# tinyTHP.net
KiCad netlist of a schematic drawn in EAGLE
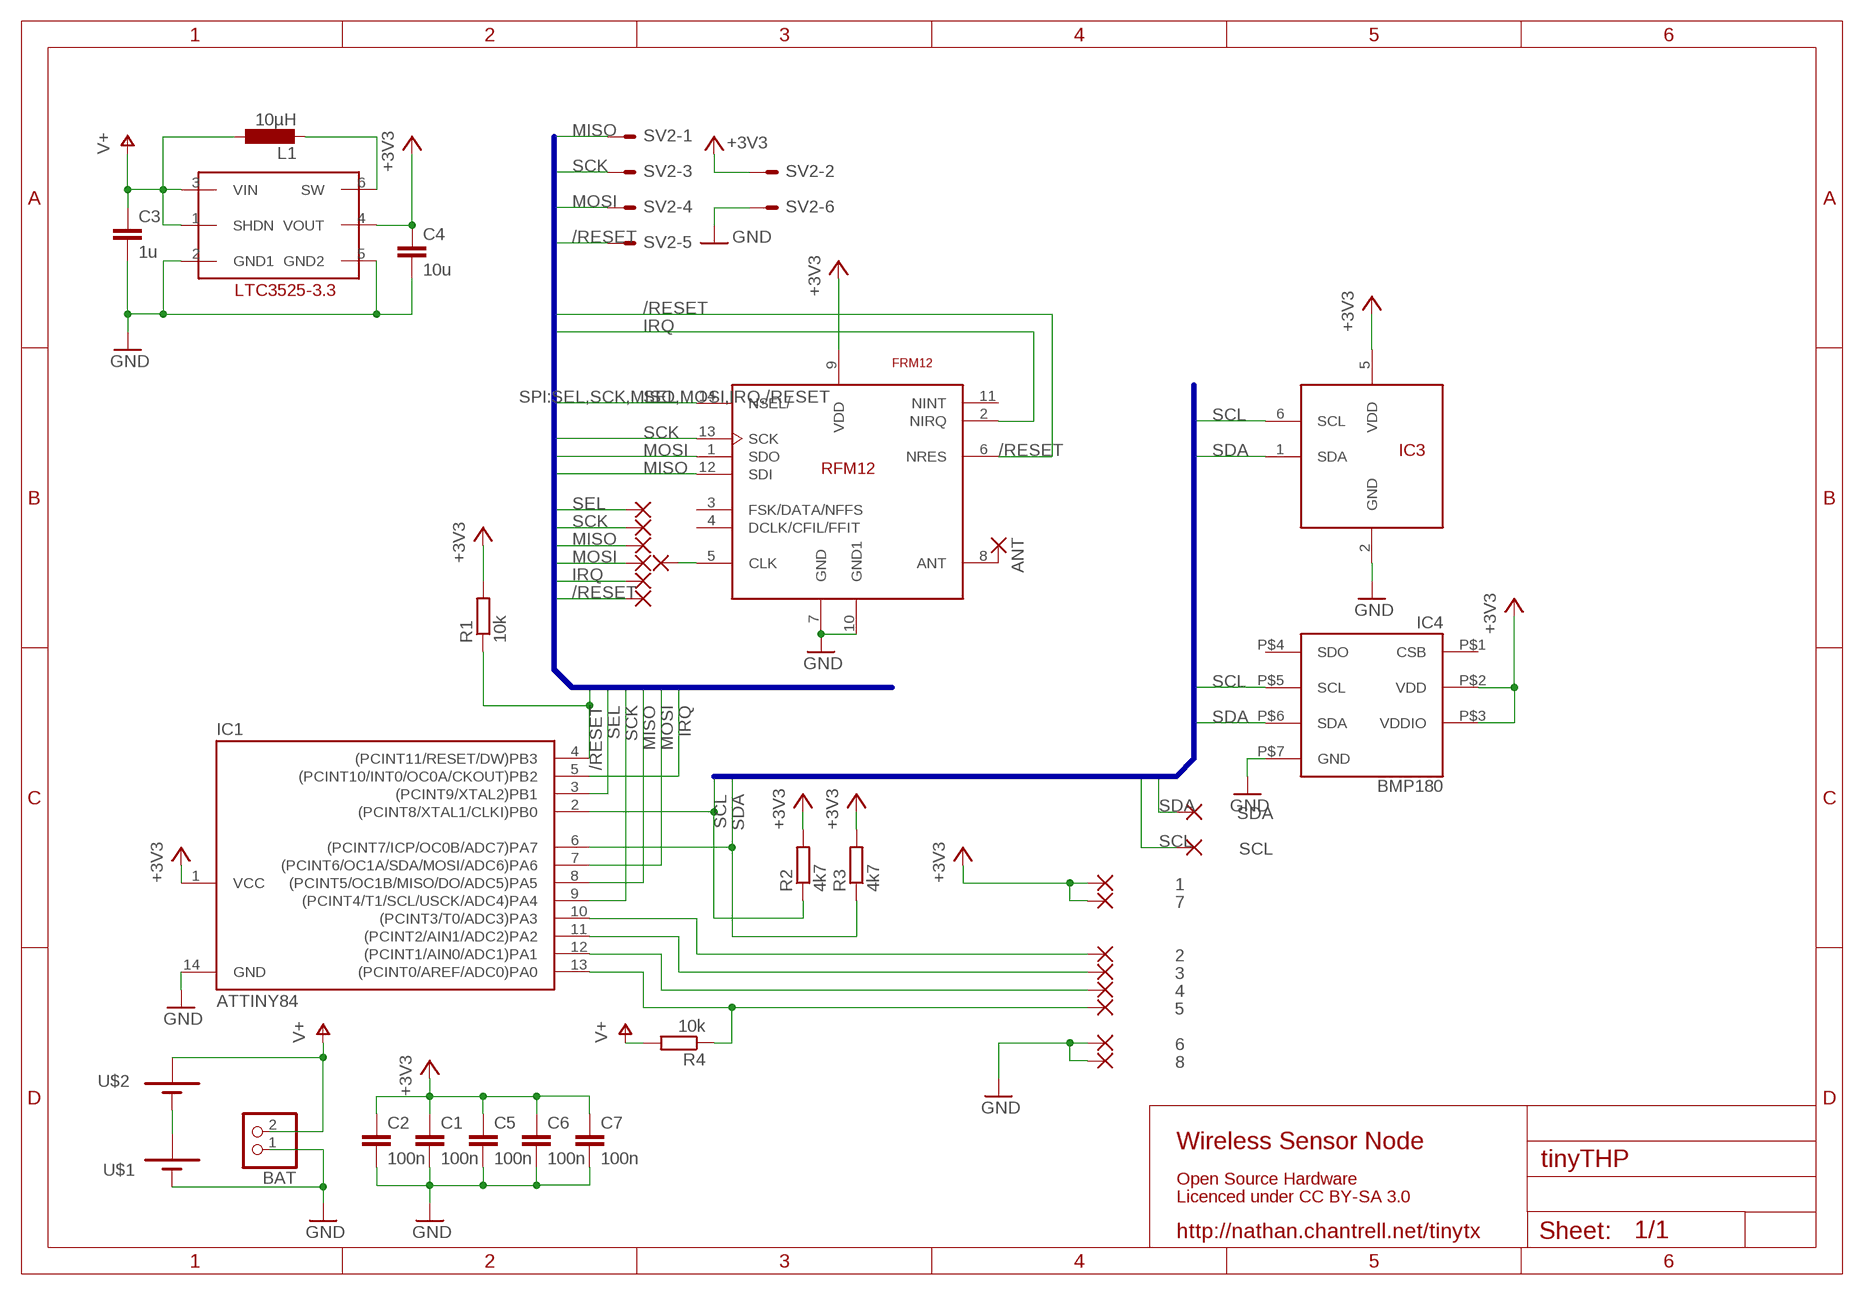
[diagram p0: schematic, sheet 1]

(export (version "E")
  (design (tool "Eeschema 10.0.6"))
  (components
    (comp (ref "/IRQ")
      (value "1,6/0,9")
      (footprint "eagle-import:1,6_0,9")
      (libsource (lib "eagle-import") (part "1,6/0,9"))
    )
    (comp (ref "/RESET")
      (value "1,6/0,9")
      (footprint "eagle-import:1,6_0,9")
      (libsource (lib "eagle-import") (part "1,6/0,9"))
    )
    (comp (ref "1")
      (value "1,6/0,9")
      (footprint "eagle-import:1,6_0,9")
      (libsource (lib "eagle-import") (part "1,6/0,9"))
    )
    (comp (ref "2")
      (value "1,6/0,9")
      (footprint "eagle-import:1,6_0,9")
      (libsource (lib "eagle-import") (part "1,6/0,9"))
    )
    (comp (ref "3")
      (value "1,6/0,9")
      (footprint "eagle-import:1,6_0,9")
      (libsource (lib "eagle-import") (part "1,6/0,9"))
    )
    (comp (ref "4")
      (value "1,6/0,9")
      (footprint "eagle-import:1,6_0,9")
      (libsource (lib "eagle-import") (part "1,6/0,9"))
    )
    (comp (ref "5")
      (value "1,6/0,9")
      (footprint "eagle-import:1,6_0,9")
      (libsource (lib "eagle-import") (part "1,6/0,9"))
    )
    (comp (ref "6")
      (value "1,6/0,9")
      (footprint "eagle-import:1,6_0,9")
      (libsource (lib "eagle-import") (part "1,6/0,9"))
    )
    (comp (ref "7")
      (value "1,6/0,9")
      (footprint "eagle-import:1,6_0,9")
      (libsource (lib "eagle-import") (part "1,6/0,9"))
    )
    (comp (ref "8")
      (value "1,6/0,9")
      (footprint "eagle-import:1,6_0,9")
      (libsource (lib "eagle-import") (part "1,6/0,9"))
    )
    (comp (ref "ANT")
      (value "1,6/0,8")
      (footprint "eagle-import:1,6_0,8")
      (libsource (lib "eagle-import") (part "1,6/0,8"))
    )
    (comp (ref "BAT")
      (value "PINHD-1X2")
      (footprint "eagle-import:1X02")
      (libsource (lib "eagle-import") (part "PINHD-1X2"))
    )
    (comp (ref "C1")
      (value "100n")
      (footprint "eagle-import:C0603")
      (libsource (lib "eagle-import") (part "C-EUC0603"))
    )
    (comp (ref "C2")
      (value "100n")
      (footprint "eagle-import:C0603")
      (libsource (lib "eagle-import") (part "C-EUC0603"))
    )
    (comp (ref "C3")
      (value "1u")
      (footprint "eagle-import:C0603")
      (libsource (lib "eagle-import") (part "C-EUC0603"))
    )
    (comp (ref "C4")
      (value "10u")
      (footprint "eagle-import:C0603")
      (libsource (lib "eagle-import") (part "C-EUC0603"))
    )
    (comp (ref "C5")
      (value "100n")
      (footprint "eagle-import:C0603")
      (libsource (lib "eagle-import") (part "C-EUC0603"))
    )
    (comp (ref "C6")
      (value "100n")
      (footprint "eagle-import:C0603")
      (libsource (lib "eagle-import") (part "C-EUC0603"))
    )
    (comp (ref "C7")
      (value "100n")
      (footprint "eagle-import:C0603")
      (libsource (lib "eagle-import") (part "C-EUC0603"))
    )
    (comp (ref "IC1")
      (value "ATTINY84")
      (footprint "eagle-import:SOIC14")
      (libsource (lib "eagle-import") (part "TINY24/44/84-SSU"))
    )
    (comp (ref "IC2")
      (value "IC2")
      (footprint "eagle-import:SC70-6")
      (libsource (lib "eagle-import") (part "LTC3525"))
    )
    (comp (ref "IC3")
      (value "SI7021")
      (footprint "eagle-import:DFN-6")
      (libsource (lib "eagle-import") (part "SI7021"))
    )
    (comp (ref "IC4")
      (value "BMP180")
      (footprint "eagle-import:LGA-7")
      (libsource (lib "eagle-import") (part "BMP180"))
    )
    (comp (ref "L1")
      (value "10µH")
      (footprint "eagle-import:L1616")
      (libsource (lib "eagle-import") (part "L-EUL1616"))
    )
    (comp (ref "MISO")
      (value "1,6/0,9")
      (footprint "eagle-import:1,6_0,9")
      (libsource (lib "eagle-import") (part "1,6/0,9"))
    )
    (comp (ref "MOSI")
      (value "1,6/0,9")
      (footprint "eagle-import:1,6_0,9")
      (libsource (lib "eagle-import") (part "1,6/0,9"))
    )
    (comp (ref "R1")
      (value "10k")
      (footprint "eagle-import:R0603")
      (libsource (lib "eagle-import") (part "R-EU_R0603"))
    )
    (comp (ref "R2")
      (value "4k7")
      (footprint "eagle-import:R0603")
      (libsource (lib "eagle-import") (part "R-EU_R0603"))
    )
    (comp (ref "R3")
      (value "4k7")
      (footprint "eagle-import:R0603")
      (libsource (lib "eagle-import") (part "R-EU_R0603"))
    )
    (comp (ref "R4")
      (value "10k")
      (footprint "eagle-import:R0603")
      (libsource (lib "eagle-import") (part "R-EU_R0603"))
    )
    (comp (ref "RFMCLK")
      (value "1,6/0,9")
      (footprint "eagle-import:1,6_0,9")
      (libsource (lib "eagle-import") (part "1,6/0,9"))
    )
    (comp (ref "SCK")
      (value "1,6/0,9")
      (footprint "eagle-import:1,6_0,9")
      (libsource (lib "eagle-import") (part "1,6/0,9"))
    )
    (comp (ref "SCL")
      (value "1,6/0,9")
      (footprint "eagle-import:1,6_0,9")
      (libsource (lib "eagle-import") (part "1,6/0,9"))
    )
    (comp (ref "SDA")
      (value "1,6/0,9")
      (footprint "eagle-import:1,6_0,9")
      (libsource (lib "eagle-import") (part "1,6/0,9"))
    )
    (comp (ref "SEL")
      (value "1,6/0,9")
      (footprint "eagle-import:1,6_0,9")
      (libsource (lib "eagle-import") (part "1,6/0,9"))
    )
    (comp (ref "SV2")
      (value "ML6E")
      (footprint "eagle-import:ML6")
      (libsource (lib "eagle-import") (part "ML6?E"))
    )
    (comp (ref "U$1")
      (value "KEYSTONE-92-AA-BATTERY-HOLDER")
      (footprint "eagle-import:KEYSTONE-92-AA-BATTERY")
      (libsource (lib "eagle-import") (part "KEYSTONE-92-AA-BATTERY-HOLDER"))
    )
    (comp (ref "U$2")
      (value "KEYSTONE-92-AA-BATTERY-HOLDER")
      (footprint "eagle-import:KEYSTONE-92-AA-BATTERY")
      (libsource (lib "eagle-import") (part "KEYSTONE-92-AA-BATTERY-HOLDER"))
    )
    (comp (ref "U$3")
      (value "FRM12")
      (footprint "eagle-import:RFM12")
      (libsource (lib "eagle-import") (part "FRM12"))
    )
  )
  (nets
    (net (code "2") (name "+3V3") (class "Default")
      (node (ref "1") (pin "1") (pinfunction "P_1") (pintype "passive"))
      (node (ref "7") (pin "1") (pinfunction "P_1") (pintype "passive"))
      (node (ref "C1") (pin "1") (pinfunction "1_1") (pintype "passive"))
      (node (ref "C2") (pin "1") (pinfunction "1_1") (pintype "passive"))
      (node (ref "C4") (pin "1") (pinfunction "1_1") (pintype "passive"))
      (node (ref "C5") (pin "1") (pinfunction "1_1") (pintype "passive"))
      (node (ref "C6") (pin "1") (pinfunction "1_1") (pintype "passive"))
      (node (ref "C7") (pin "1") (pinfunction "1_1") (pintype "passive"))
      (node (ref "IC1") (pin "1") (pinfunction "VCC_1") (pintype "power_in"))
      (node (ref "IC2") (pin "4") (pinfunction "VOUT_4") (pintype "bidirectional"))
      (node (ref "IC3") (pin "5") (pinfunction "VDD_5") (pintype "power_in"))
      (node (ref "IC4") (pin "P$2") (pinfunction "VDD_P$2") (pintype "bidirectional"))
      (node (ref "IC4") (pin "P$3") (pinfunction "VDDIO_P$3") (pintype "bidirectional"))
      (node (ref "R1") (pin "2") (pinfunction "2_2") (pintype "passive"))
      (node (ref "R2") (pin "2") (pinfunction "2_2") (pintype "passive"))
      (node (ref "R3") (pin "2") (pinfunction "2_2") (pintype "passive"))
      (node (ref "SV2") (pin "2") (pinfunction "S_2") (pintype "passive"))
      (node (ref "U$3") (pin "9") (pinfunction "VDD_9") (pintype "power_in"))
    )
    (net (code "3") (name "/IRQ") (class "Default")
      (node (ref "/IRQ") (pin "1") (pinfunction "P_1") (pintype "passive"))
      (node (ref "IC1") (pin "5") (pinfunction "(PCINT10/INT0/OC0A/CKOUT)PB2_5") (pintype "bidirectional"))
      (node (ref "U$3") (pin "2") (pinfunction "NIRQ_2") (pintype "output"))
    )
    (net (code "4") (name "/MISO") (class "Default")
      (node (ref "IC1") (pin "8") (pinfunction "(PCINT5/OC1B/MISO/DO/ADC5)PA5_8") (pintype "bidirectional"))
      (node (ref "MISO") (pin "1") (pinfunction "P_1") (pintype "passive"))
      (node (ref "SV2") (pin "1") (pinfunction "S_1") (pintype "passive"))
      (node (ref "U$3") (pin "12") (pinfunction "SDI_12") (pintype "input"))
    )
    (net (code "5") (name "/MOSI") (class "Default")
      (node (ref "IC1") (pin "7") (pinfunction "(PCINT6/OC1A/SDA/MOSI/ADC6)PA6_7") (pintype "bidirectional"))
      (node (ref "MOSI") (pin "1") (pinfunction "P_1") (pintype "passive"))
      (node (ref "SV2") (pin "4") (pinfunction "S_4") (pintype "passive"))
      (node (ref "U$3") (pin "1") (pinfunction "SDO_1") (pintype "output"))
    )
    (net (code "6") (name "/SCK") (class "Default")
      (node (ref "IC1") (pin "9") (pinfunction "(PCINT4/T1/SCL/USCK/ADC4)PA4_9") (pintype "bidirectional"))
      (node (ref "SCK") (pin "1") (pinfunction "P_1") (pintype "passive"))
      (node (ref "SV2") (pin "3") (pinfunction "S_3") (pintype "passive"))
      (node (ref "U$3") (pin "13") (pinfunction "SCK_13") (pintype "input"))
    )
    (net (code "7") (name "/SCL") (class "Default")
      (node (ref "IC1") (pin "2") (pinfunction "(PCINT8/XTAL1/CLKI)PB0_2") (pintype "bidirectional"))
      (node (ref "IC3") (pin "6") (pinfunction "SCL_6") (pintype "bidirectional"))
      (node (ref "IC4") (pin "P$5") (pinfunction "SCL_P$5") (pintype "bidirectional"))
      (node (ref "R2") (pin "1") (pinfunction "1_1") (pintype "passive"))
      (node (ref "SCL") (pin "1") (pinfunction "P_1") (pintype "passive"))
    )
    (net (code "8") (name "/SDA") (class "Default")
      (node (ref "IC1") (pin "6") (pinfunction "(PCINT7/ICP/OC0B/ADC7)PA7_6") (pintype "bidirectional"))
      (node (ref "IC3") (pin "1") (pinfunction "SDA_1") (pintype "bidirectional"))
      (node (ref "IC4") (pin "P$6") (pinfunction "SDA_P$6") (pintype "bidirectional"))
      (node (ref "R3") (pin "1") (pinfunction "1_1") (pintype "passive"))
      (node (ref "SDA") (pin "1") (pinfunction "P_1") (pintype "passive"))
    )
    (net (code "9") (name "/SEL") (class "Default")
      (node (ref "IC1") (pin "3") (pinfunction "(PCINT9/XTAL2)PB1_3") (pintype "bidirectional"))
      (node (ref "SEL") (pin "1") (pinfunction "P_1") (pintype "passive"))
      (node (ref "U$3") (pin "14") (pinfunction "NSEL/_14") (pintype "input"))
    )
    (net (code "11") (name "/{slash}RESET") (class "Default")
      (node (ref "/RESET") (pin "1") (pinfunction "P_1") (pintype "passive"))
      (node (ref "IC1") (pin "4") (pinfunction "(PCINT11/RESET/DW)PB3_4") (pintype "bidirectional"))
      (node (ref "R1") (pin "1") (pinfunction "1_1") (pintype "passive"))
      (node (ref "SV2") (pin "5") (pinfunction "S_5") (pintype "passive"))
      (node (ref "U$3") (pin "6") (pinfunction "NRES_6") (pintype "bidirectional"))
    )
    (net (code "12") (name "GND") (class "Default")
      (node (ref "6") (pin "1") (pinfunction "P_1") (pintype "passive"))
      (node (ref "8") (pin "1") (pinfunction "P_1") (pintype "passive"))
      (node (ref "BAT") (pin "1") (pinfunction "1_1") (pintype "passive"))
      (node (ref "C1") (pin "2") (pinfunction "2_2") (pintype "passive"))
      (node (ref "C2") (pin "2") (pinfunction "2_2") (pintype "passive"))
      (node (ref "C3") (pin "2") (pinfunction "2_2") (pintype "passive"))
      (node (ref "C4") (pin "2") (pinfunction "2_2") (pintype "passive"))
      (node (ref "C5") (pin "2") (pinfunction "2_2") (pintype "passive"))
      (node (ref "C6") (pin "2") (pinfunction "2_2") (pintype "passive"))
      (node (ref "C7") (pin "2") (pinfunction "2_2") (pintype "passive"))
      (node (ref "IC1") (pin "14") (pinfunction "GND_14") (pintype "power_in"))
      (node (ref "IC2") (pin "2") (pinfunction "GND1_2") (pintype "bidirectional"))
      (node (ref "IC2") (pin "5") (pinfunction "GND2_5") (pintype "bidirectional"))
      (node (ref "IC3") (pin "2") (pinfunction "GND_2") (pintype "power_in"))
      (node (ref "IC4") (pin "P$7") (pinfunction "GND_P$7") (pintype "bidirectional"))
      (node (ref "SV2") (pin "6") (pinfunction "S_6") (pintype "passive"))
      (node (ref "U$1") (pin "GND") (pinfunction "-_GND") (pintype "power_in"))
      (node (ref "U$1") (pin "GND2") (pinfunction "-_GND2") (pintype "power_in"))
      (node (ref "U$3") (pin "10") (pinfunction "GND1_10") (pintype "passive"))
      (node (ref "U$3") (pin "7") (pinfunction "GND_7") (pintype "passive"))
    )
    (net (code "13") (name "Net-(2-P)") (class "Default")
      (node (ref "2") (pin "1") (pinfunction "P_1") (pintype "passive"))
      (node (ref "IC1") (pin "10") (pinfunction "(PCINT3/T0/ADC3)PA3_10") (pintype "bidirectional"))
    )
    (net (code "14") (name "Net-(3-P)") (class "Default")
      (node (ref "3") (pin "1") (pinfunction "P_1") (pintype "passive"))
      (node (ref "IC1") (pin "11") (pinfunction "(PCINT2/AIN1/ADC2)PA2_11") (pintype "bidirectional"))
    )
    (net (code "15") (name "Net-(4-P)") (class "Default")
      (node (ref "4") (pin "1") (pinfunction "P_1") (pintype "passive"))
      (node (ref "IC1") (pin "12") (pinfunction "(PCINT1/AIN0/ADC1)PA1_12") (pintype "bidirectional"))
    )
    (net (code "16") (name "Net-(5-P)") (class "Default")
      (node (ref "5") (pin "1") (pinfunction "P_1") (pintype "passive"))
      (node (ref "IC1") (pin "13") (pinfunction "(PCINT0/AREF/ADC0)PA0_13") (pintype "bidirectional"))
      (node (ref "R4") (pin "1") (pinfunction "1_1") (pintype "passive"))
    )
    (net (code "17") (name "Net-(ANT-P)") (class "Default")
      (node (ref "ANT") (pin "1") (pinfunction "P_1") (pintype "passive"))
      (node (ref "U$3") (pin "8") (pinfunction "ANT_8") (pintype "bidirectional"))
    )
    (net (code "18") (name "Net-(IC2-SW)") (class "Default")
      (node (ref "IC2") (pin "6") (pinfunction "SW_6") (pintype "bidirectional"))
      (node (ref "L1") (pin "P$2") (pinfunction "2_P$2") (pintype "passive"))
    )
    (net (code "19") (name "Net-(RFMCLK-P)") (class "Default")
      (node (ref "RFMCLK") (pin "1") (pinfunction "P_1") (pintype "passive"))
      (node (ref "U$3") (pin "5") (pinfunction "CLK_5") (pintype "output"))
    )
    (net (code "20") (name "Net-(U$1-+-PadVBATT)") (class "Default")
      (node (ref "U$1") (pin "VBATT") (pinfunction "+_VBATT") (pintype "power_in"))
      (node (ref "U$1") (pin "VBATT1") (pinfunction "+_VBATT1") (pintype "power_in"))
      (node (ref "U$2") (pin "GND") (pinfunction "-_GND") (pintype "power_in"))
      (node (ref "U$2") (pin "GND2") (pinfunction "-_GND2") (pintype "power_in"))
    )
    (net (code "21") (name "V+") (class "Default")
      (node (ref "BAT") (pin "2") (pinfunction "2_2") (pintype "passive"))
      (node (ref "C3") (pin "1") (pinfunction "1_1") (pintype "passive"))
      (node (ref "IC2") (pin "1") (pinfunction "SHDN_1") (pintype "bidirectional"))
      (node (ref "IC2") (pin "3") (pinfunction "VIN_3") (pintype "bidirectional"))
      (node (ref "L1") (pin "P$1") (pinfunction "1_P$1") (pintype "passive"))
      (node (ref "R4") (pin "2") (pinfunction "2_2") (pintype "passive"))
      (node (ref "U$2") (pin "VBATT") (pinfunction "+_VBATT") (pintype "power_in"))
      (node (ref "U$2") (pin "VBATT1") (pinfunction "+_VBATT1") (pintype "power_in"))
    )
    (net (code "22") (name "unconnected-(IC4-CSB-PadP$1)") (class "Default")
      (node (ref "IC4") (pin "P$1") (pinfunction "CSB_P$1") (pintype "bidirectional"))
    )
    (net (code "23") (name "unconnected-(IC4-SDO-PadP$4)") (class "Default")
      (node (ref "IC4") (pin "P$4") (pinfunction "SDO_P$4") (pintype "bidirectional"))
    )
    (net (code "24") (name "unconnected-(U$3-DCLK{slash}CFIL{slash}FFIT-Pad4)") (class "Default")
      (node (ref "U$3") (pin "4") (pinfunction "DCLK/CFIL/FFIT_4") (pintype "bidirectional"))
    )
    (net (code "25") (name "unconnected-(U$3-FSK{slash}DATA{slash}NFFS-Pad3)") (class "Default")
      (node (ref "U$3") (pin "3") (pinfunction "FSK/DATA/NFFS_3") (pintype "bidirectional"))
    )
    (net (code "26") (name "unconnected-(U$3-NINT-Pad11)") (class "Default")
      (node (ref "U$3") (pin "11") (pinfunction "NINT_11") (pintype "bidirectional"))
    )
  )
)
